# MIPI_CSI.net
KiCad netlist of a schematic drawn in Altium Designer
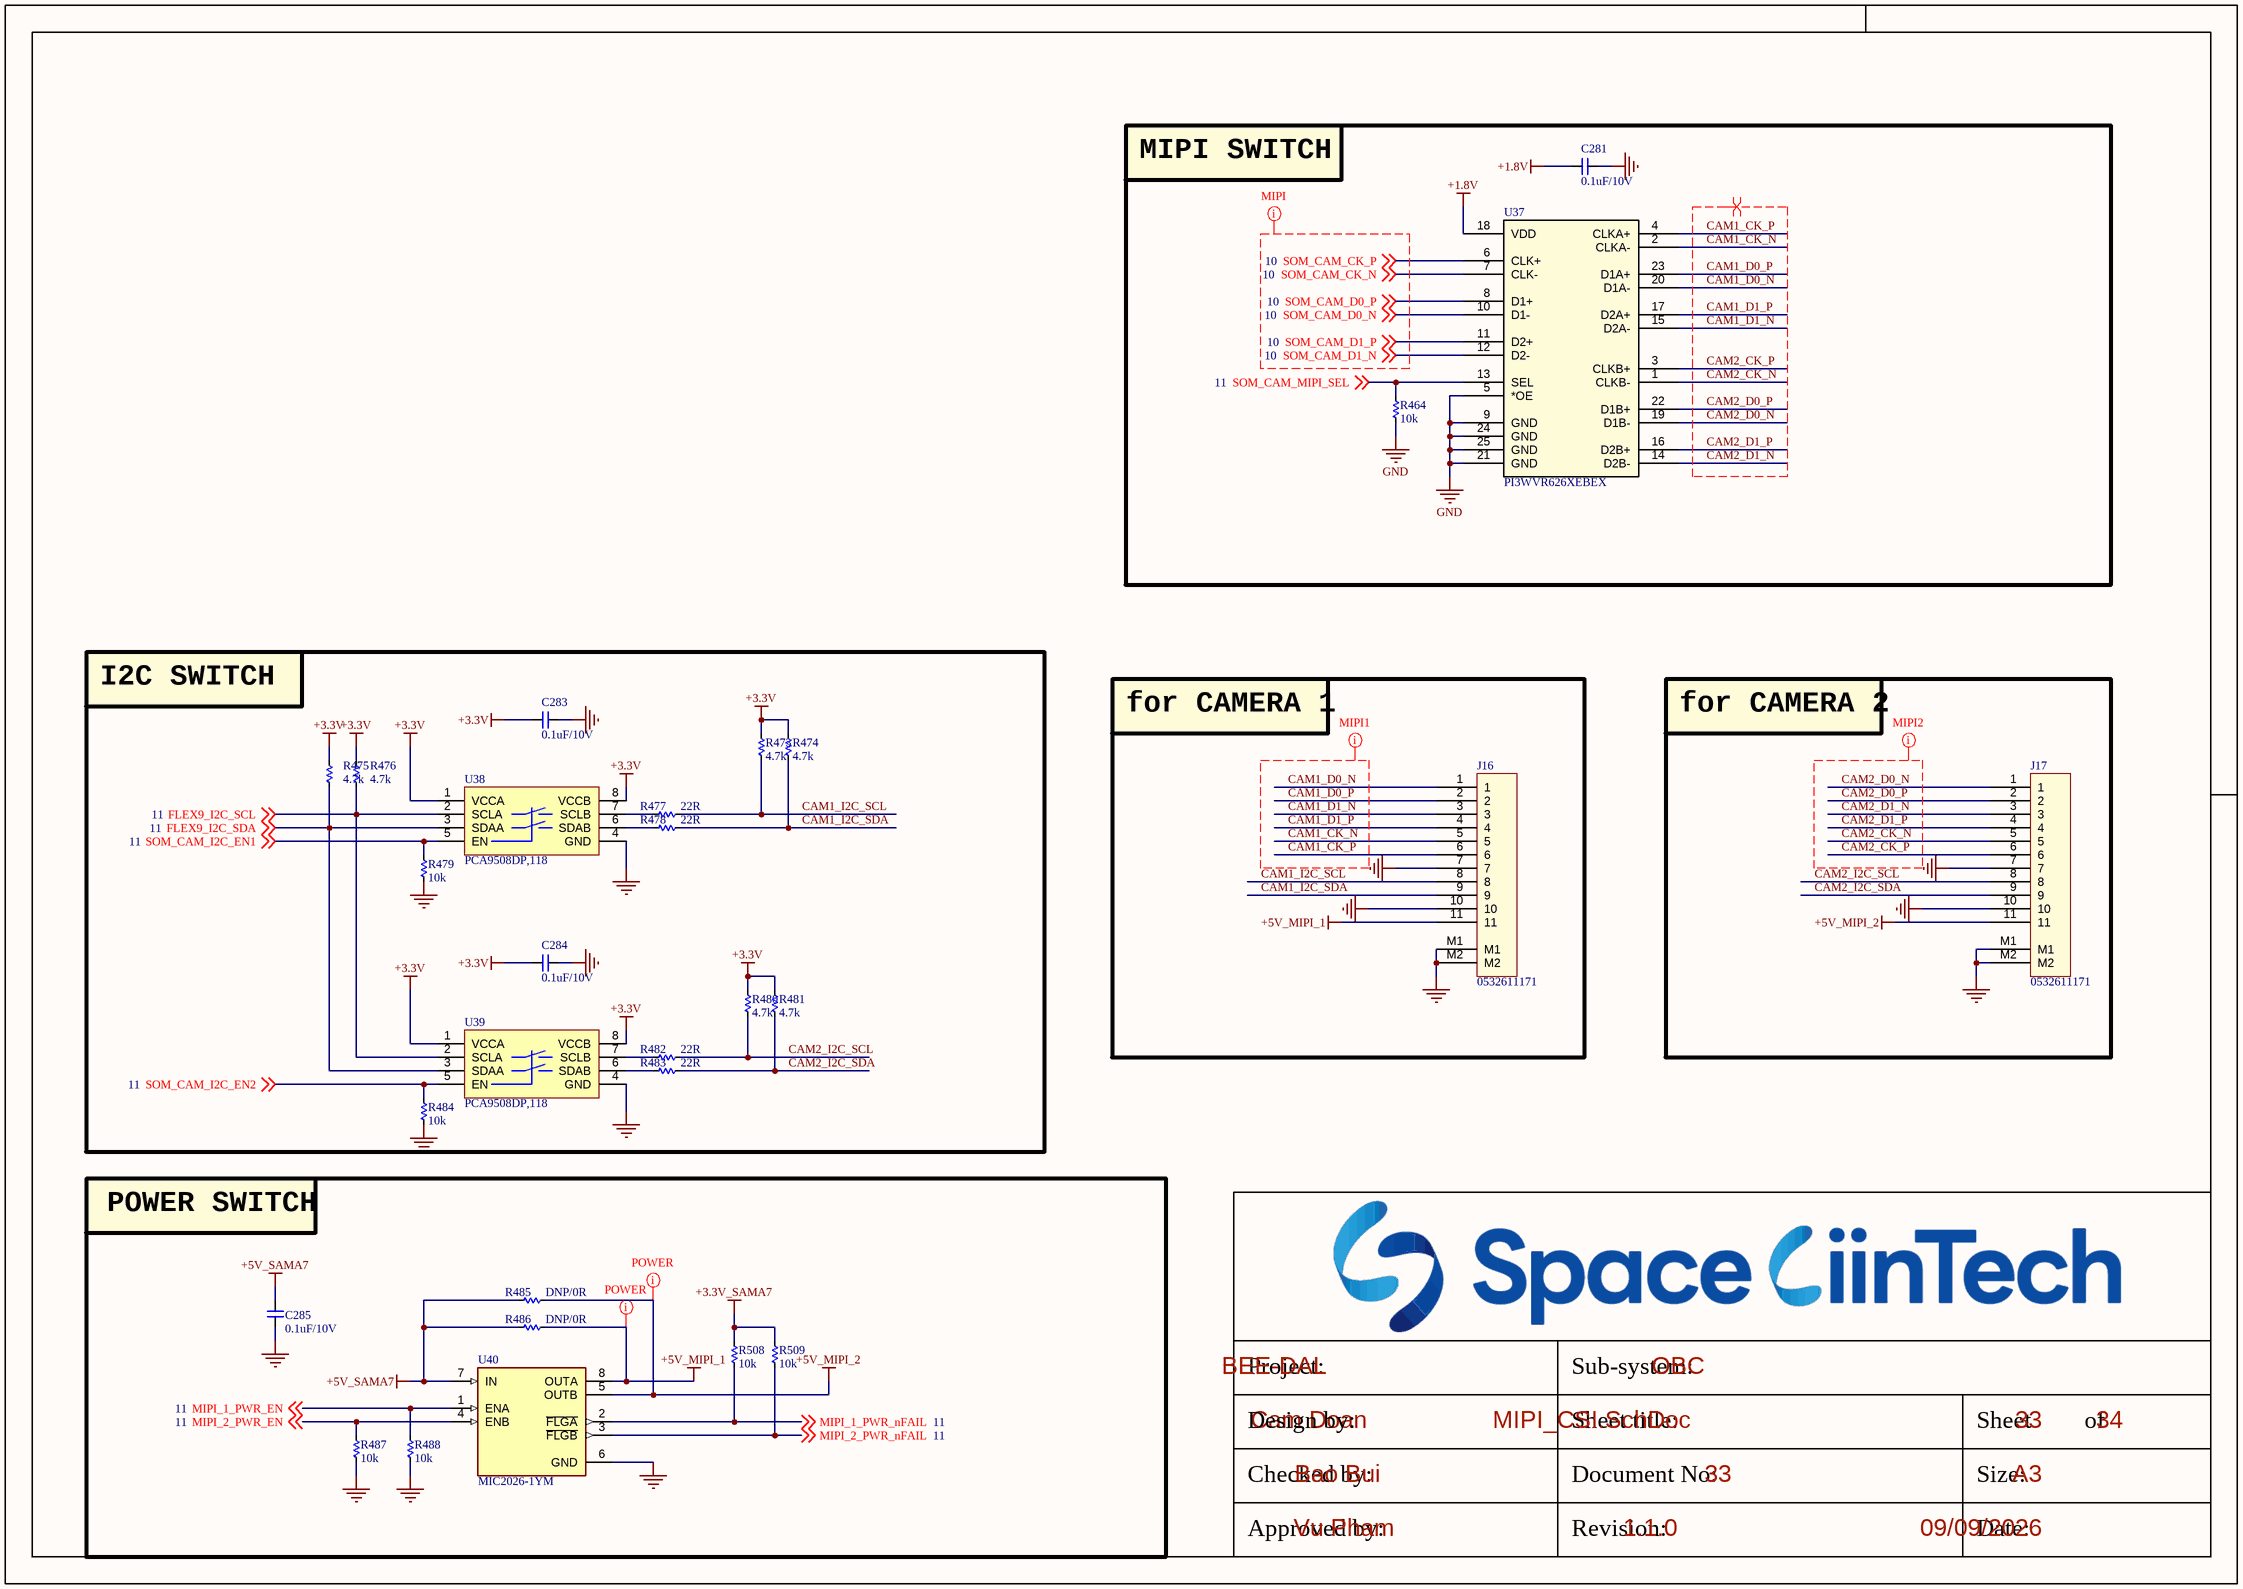
[diagram p0: MIPI_CSI.SchDoc]

(export (version "E")
  (design (tool "Eeschema 10.0.6"))
  (components
    (comp (ref "C281")
      (value "0.1uF/10V")
      (footprint "CAP_C_1005X50_L")
      (description "CAP CHIP")
      (libsource (lib "LABLIB") (part "_CAP_C_2"))
    )
    (comp (ref "C283")
      (value "0.1uF/10V")
      (footprint "CAP_C_1005X50_L")
      (description "CAP CHIP")
      (libsource (lib "LABLIB") (part "_CAP_C_2"))
    )
    (comp (ref "C284")
      (value "0.1uF/10V")
      (footprint "CAP_C_1005X50_L")
      (description "CAP CHIP")
      (libsource (lib "LABLIB") (part "_CAP_C_2"))
    )
    (comp (ref "C285")
      (value "0.1uF/10V")
      (footprint "CAP_C_1005X50_L")
      (description "CAP")
      (libsource (lib "LABLIB") (part "_CAP_C_2"))
    )
    (comp (ref "J16")
      (value "0532611171")
      (footprint "MOLEX_0532611171")
      (libsource (lib "LABLIB") (part "Header 11x1_2M"))
    )
    (comp (ref "J17")
      (value "0532611171")
      (footprint "MOLEX_0532611171")
      (libsource (lib "LABLIB") (part "Header 11x1_2M"))
    )
    (comp (ref "R464")
      (value "10k")
      (footprint "RES_C_1005X40")
      (description "RES")
      (libsource (lib "LABLIB") (part "_RES_B_2"))
    )
    (comp (ref "R473")
      (value "4.7k")
      (footprint "RES_C_1005X40")
      (description "RES")
      (libsource (lib "LABLIB") (part "_RES_B_2"))
    )
    (comp (ref "R474")
      (value "4.7k")
      (footprint "RES_C_1005X40")
      (description "RES")
      (libsource (lib "LABLIB") (part "_RES_B_2"))
    )
    (comp (ref "R475")
      (value "4.7k")
      (footprint "RES_C_1005X40")
      (description "RES")
      (libsource (lib "LABLIB") (part "_RES_B_2"))
    )
    (comp (ref "R476")
      (value "4.7k")
      (footprint "RES_C_1005X40")
      (description "RES")
      (libsource (lib "LABLIB") (part "_RES_B_2"))
    )
    (comp (ref "R477")
      (value "22R")
      (footprint "RES_C_1005X40")
      (description "RES")
      (libsource (lib "LABLIB") (part "_RES_B_2"))
    )
    (comp (ref "R478")
      (value "22R")
      (footprint "RES_C_1005X40")
      (description "RES")
      (libsource (lib "LABLIB") (part "_RES_B_2"))
    )
    (comp (ref "R479")
      (value "10k")
      (footprint "RES_C_1005X40")
      (description "RES")
      (libsource (lib "LABLIB") (part "_RES_B_2"))
    )
    (comp (ref "R480")
      (value "4.7k")
      (footprint "RES_C_1005X40")
      (description "RES")
      (libsource (lib "LABLIB") (part "_RES_B_2"))
    )
    (comp (ref "R481")
      (value "4.7k")
      (footprint "RES_C_1005X40")
      (description "RES")
      (libsource (lib "LABLIB") (part "_RES_B_2"))
    )
    (comp (ref "R482")
      (value "22R")
      (footprint "RES_C_1005X40")
      (description "RES")
      (libsource (lib "LABLIB") (part "_RES_B_2"))
    )
    (comp (ref "R483")
      (value "22R")
      (footprint "RES_C_1005X40")
      (description "RES")
      (libsource (lib "LABLIB") (part "_RES_B_2"))
    )
    (comp (ref "R484")
      (value "10k")
      (footprint "RES_C_1005X40")
      (description "RES")
      (libsource (lib "LABLIB") (part "_RES_B_2"))
    )
    (comp (ref "R485")
      (value "DNP/0R")
      (footprint "RES_C_1005X40")
      (description "RES")
      (libsource (lib "LABLIB") (part "_RES_B_2"))
    )
    (comp (ref "R486")
      (value "DNP/0R")
      (footprint "RES_C_1005X40")
      (description "RES")
      (libsource (lib "LABLIB") (part "_RES_B_2"))
    )
    (comp (ref "R487")
      (value "10k")
      (footprint "RES_C_1005X40")
      (description "RES")
      (libsource (lib "LABLIB") (part "_RES_B_2"))
    )
    (comp (ref "R488")
      (value "10k")
      (footprint "RES_C_1005X40")
      (description "RES")
      (libsource (lib "LABLIB") (part "_RES_B_2"))
    )
    (comp (ref "R508")
      (value "10k")
      (footprint "RES_C_1005X40")
      (description "RES")
      (libsource (lib "LABLIB") (part "_RES_B_2"))
    )
    (comp (ref "R509")
      (value "10k")
      (footprint "RES_C_1005X40")
      (description "RES")
      (libsource (lib "LABLIB") (part "_RES_B_2"))
    )
    (comp (ref "U37")
      (value "PI3WVR626XEBEX")
      (footprint "PI3WVR626XEBEX_DIO")
      (libsource (lib "CAMERA_SchLib") (part "PI3WVR626XEBEX"))
    )
    (comp (ref "U38")
      (value "PCA9508DP,118")
      (footprint "TSOP8")
      (libsource (lib "EXP_HW_V3") (part "PCA9508DP,118"))
    )
    (comp (ref "U39")
      (value "PCA9508DP,118")
      (footprint "TSOP8")
      (libsource (lib "EXP_HW_V3") (part "PCA9508DP,118"))
    )
    (comp (ref "U40")
      (value "MIC2026-1YM")
      (footprint "SOIC127P602X173-8N")
      (description "Power Switch/Driver 1:2 N-Channel 1.25A 8-SOIC")
      (fields (field (name "MF") "Microchip"))
      (libsource (lib "LABLIB") (part "IC_PWRSW_MIC2026-1YM"))
    )
  )
  (nets
    (net (code "1") (name "+1.8V") (class "Default")
      (node (ref "C281") (pin "2") (pinfunction "2_2") (pintype "passive"))
      (node (ref "U37") (pin "18") (pinfunction "VDD_18") (pintype "passive"))
    )
    (net (code "2") (name "+3.3V") (class "Default")
      (node (ref "C283") (pin "2") (pinfunction "2_2") (pintype "passive"))
      (node (ref "C284") (pin "2") (pinfunction "2_2") (pintype "passive"))
      (node (ref "R473") (pin "1") (pinfunction "1_1") (pintype "passive"))
      (node (ref "R474") (pin "1") (pinfunction "1_1") (pintype "passive"))
      (node (ref "R475") (pin "1") (pinfunction "1_1") (pintype "passive"))
      (node (ref "R476") (pin "1") (pinfunction "1_1") (pintype "passive"))
      (node (ref "R480") (pin "1") (pinfunction "1_1") (pintype "passive"))
      (node (ref "R481") (pin "1") (pinfunction "1_1") (pintype "passive"))
      (node (ref "U38") (pin "1") (pinfunction "VCCA_1") (pintype "passive"))
      (node (ref "U38") (pin "8") (pinfunction "VCCB_8") (pintype "passive"))
      (node (ref "U39") (pin "1") (pinfunction "VCCA_1") (pintype "passive"))
      (node (ref "U39") (pin "8") (pinfunction "VCCB_8") (pintype "passive"))
    )
    (net (code "3") (name "+3.3V_SAMA7") (class "Default")
      (node (ref "R508") (pin "1") (pinfunction "1_1") (pintype "passive"))
      (node (ref "R509") (pin "1") (pinfunction "1_1") (pintype "passive"))
    )
    (net (code "4") (name "+5V_MIPI_1") (class "Default")
      (node (ref "J16") (pin "11") (pinfunction "11_11") (pintype "passive"))
      (node (ref "R486") (pin "1") (pinfunction "1_1") (pintype "passive"))
      (node (ref "U40") (pin "8") (pinfunction "OUTA_8") (pintype "passive"))
    )
    (net (code "5") (name "+5V_MIPI_2") (class "Default")
      (node (ref "J17") (pin "11") (pinfunction "11_11") (pintype "passive"))
      (node (ref "R485") (pin "1") (pinfunction "1_1") (pintype "passive"))
      (node (ref "U40") (pin "5") (pinfunction "OUTB_5") (pintype "passive"))
    )
    (net (code "6") (name "+5V_SAMA7") (class "Default")
      (node (ref "C285") (pin "2") (pinfunction "2_2") (pintype "passive"))
      (node (ref "R485") (pin "2") (pinfunction "2_2") (pintype "passive"))
      (node (ref "R486") (pin "2") (pinfunction "2_2") (pintype "passive"))
      (node (ref "U40") (pin "7") (pinfunction "IN_7") (pintype "input"))
    )
    (net (code "7") (name "/CAM1_CK_N") (class "Default")
      (node (ref "J16") (pin "5") (pinfunction "5_5") (pintype "passive"))
      (node (ref "U37") (pin "2") (pinfunction "CLKA-_2") (pintype "passive"))
    )
    (net (code "8") (name "/CAM1_CK_P") (class "Default")
      (node (ref "J16") (pin "6") (pinfunction "6_6") (pintype "passive"))
      (node (ref "U37") (pin "4") (pinfunction "CLKA+_4") (pintype "passive"))
    )
    (net (code "9") (name "/CAM1_D0_N") (class "Default")
      (node (ref "J16") (pin "1") (pinfunction "1_1") (pintype "passive"))
      (node (ref "U37") (pin "20") (pinfunction "D1A-_20") (pintype "passive"))
    )
    (net (code "10") (name "/CAM1_D0_P") (class "Default")
      (node (ref "J16") (pin "2") (pinfunction "2_2") (pintype "passive"))
      (node (ref "U37") (pin "23") (pinfunction "D1A+_23") (pintype "passive"))
    )
    (net (code "11") (name "/CAM1_D1_N") (class "Default")
      (node (ref "J16") (pin "3") (pinfunction "3_3") (pintype "passive"))
      (node (ref "U37") (pin "15") (pinfunction "D2A-_15") (pintype "passive"))
    )
    (net (code "12") (name "/CAM1_D1_P") (class "Default")
      (node (ref "J16") (pin "4") (pinfunction "4_4") (pintype "passive"))
      (node (ref "U37") (pin "17") (pinfunction "D2A+_17") (pintype "passive"))
    )
    (net (code "13") (name "/CAM1_I2C_SCL") (class "Default")
      (node (ref "J16") (pin "8") (pinfunction "8_8") (pintype "passive"))
      (node (ref "R473") (pin "2") (pinfunction "2_2") (pintype "passive"))
      (node (ref "R477") (pin "2") (pinfunction "2_2") (pintype "passive"))
    )
    (net (code "14") (name "/CAM1_I2C_SDA") (class "Default")
      (node (ref "J16") (pin "9") (pinfunction "9_9") (pintype "passive"))
      (node (ref "R474") (pin "2") (pinfunction "2_2") (pintype "passive"))
      (node (ref "R478") (pin "2") (pinfunction "2_2") (pintype "passive"))
    )
    (net (code "15") (name "/CAM2_CK_N") (class "Default")
      (node (ref "J17") (pin "5") (pinfunction "5_5") (pintype "passive"))
      (node (ref "U37") (pin "1") (pinfunction "CLKB-_1") (pintype "passive"))
    )
    (net (code "16") (name "/CAM2_CK_P") (class "Default")
      (node (ref "J17") (pin "6") (pinfunction "6_6") (pintype "passive"))
      (node (ref "U37") (pin "3") (pinfunction "CLKB+_3") (pintype "passive"))
    )
    (net (code "17") (name "/CAM2_D0_N") (class "Default")
      (node (ref "J17") (pin "1") (pinfunction "1_1") (pintype "passive"))
      (node (ref "U37") (pin "19") (pinfunction "D1B-_19") (pintype "passive"))
    )
    (net (code "18") (name "/CAM2_D0_P") (class "Default")
      (node (ref "J17") (pin "2") (pinfunction "2_2") (pintype "passive"))
      (node (ref "U37") (pin "22") (pinfunction "D1B+_22") (pintype "passive"))
    )
    (net (code "19") (name "/CAM2_D1_N") (class "Default")
      (node (ref "J17") (pin "3") (pinfunction "3_3") (pintype "passive"))
      (node (ref "U37") (pin "14") (pinfunction "D2B-_14") (pintype "passive"))
    )
    (net (code "20") (name "/CAM2_D1_P") (class "Default")
      (node (ref "J17") (pin "4") (pinfunction "4_4") (pintype "passive"))
      (node (ref "U37") (pin "16") (pinfunction "D2B+_16") (pintype "passive"))
    )
    (net (code "21") (name "/CAM2_I2C_SCL") (class "Default")
      (node (ref "J17") (pin "8") (pinfunction "8_8") (pintype "passive"))
      (node (ref "R480") (pin "2") (pinfunction "2_2") (pintype "passive"))
      (node (ref "R482") (pin "2") (pinfunction "2_2") (pintype "passive"))
    )
    (net (code "22") (name "/CAM2_I2C_SDA") (class "Default")
      (node (ref "J17") (pin "9") (pinfunction "9_9") (pintype "passive"))
      (node (ref "R481") (pin "2") (pinfunction "2_2") (pintype "passive"))
      (node (ref "R483") (pin "2") (pinfunction "2_2") (pintype "passive"))
    )
    (net (code "23") (name "FLEX9_I2C_SCL") (class "Default")
      (node (ref "R476") (pin "2") (pinfunction "2_2") (pintype "passive"))
      (node (ref "U38") (pin "2") (pinfunction "SCLA_2") (pintype "passive"))
      (node (ref "U39") (pin "2") (pinfunction "SCLA_2") (pintype "passive"))
    )
    (net (code "24") (name "FLEX9_I2C_SDA") (class "Default")
      (node (ref "R475") (pin "2") (pinfunction "2_2") (pintype "passive"))
      (node (ref "U38") (pin "3") (pinfunction "SDAA_3") (pintype "passive"))
      (node (ref "U39") (pin "3") (pinfunction "SDAA_3") (pintype "passive"))
    )
    (net (code "25") (name "GND") (class "Default")
      (node (ref "C281") (pin "1") (pinfunction "1_1") (pintype "passive"))
      (node (ref "C283") (pin "1") (pinfunction "1_1") (pintype "passive"))
      (node (ref "C284") (pin "1") (pinfunction "1_1") (pintype "passive"))
      (node (ref "C285") (pin "1") (pinfunction "1_1") (pintype "passive"))
      (node (ref "J16") (pin "10") (pinfunction "10_10") (pintype "passive"))
      (node (ref "J16") (pin "7") (pinfunction "7_7") (pintype "passive"))
      (node (ref "J16") (pin "M1") (pinfunction "M1_M1") (pintype "passive"))
      (node (ref "J16") (pin "M2") (pinfunction "M2_M2") (pintype "passive"))
      (node (ref "J17") (pin "10") (pinfunction "10_10") (pintype "passive"))
      (node (ref "J17") (pin "7") (pinfunction "7_7") (pintype "passive"))
      (node (ref "J17") (pin "M1") (pinfunction "M1_M1") (pintype "passive"))
      (node (ref "J17") (pin "M2") (pinfunction "M2_M2") (pintype "passive"))
      (node (ref "R464") (pin "1") (pinfunction "1_1") (pintype "passive"))
      (node (ref "R479") (pin "2") (pinfunction "2_2") (pintype "passive"))
      (node (ref "R484") (pin "2") (pinfunction "2_2") (pintype "passive"))
      (node (ref "R487") (pin "2") (pinfunction "2_2") (pintype "passive"))
      (node (ref "R488") (pin "2") (pinfunction "2_2") (pintype "passive"))
      (node (ref "U37") (pin "21") (pinfunction "GND_21") (pintype "passive"))
      (node (ref "U37") (pin "24") (pinfunction "GND_24") (pintype "passive"))
      (node (ref "U37") (pin "25") (pinfunction "GND_25") (pintype "passive"))
      (node (ref "U37") (pin "5") (pinfunction "*OE_5") (pintype "passive"))
      (node (ref "U37") (pin "9") (pinfunction "GND_9") (pintype "passive"))
      (node (ref "U38") (pin "4") (pinfunction "GND_4") (pintype "passive"))
      (node (ref "U39") (pin "4") (pinfunction "GND_4") (pintype "passive"))
      (node (ref "U40") (pin "6") (pinfunction "GND_6") (pintype "power_in"))
    )
    (net (code "26") (name "MIPI_1_PWR_EN") (class "Default")
      (node (ref "R488") (pin "1") (pinfunction "1_1") (pintype "passive"))
      (node (ref "U40") (pin "1") (pinfunction "ENA_1") (pintype "input"))
    )
    (net (code "27") (name "MIPI_1_PWR_nFAIL") (class "Default")
      (node (ref "R508") (pin "2") (pinfunction "2_2") (pintype "passive"))
      (node (ref "U40") (pin "2") (pinfunction "~{FLGA}_2") (pintype "output"))
    )
    (net (code "28") (name "MIPI_2_PWR_EN") (class "Default")
      (node (ref "R487") (pin "1") (pinfunction "1_1") (pintype "passive"))
      (node (ref "U40") (pin "4") (pinfunction "ENB_4") (pintype "input"))
    )
    (net (code "29") (name "MIPI_2_PWR_nFAIL") (class "Default")
      (node (ref "R509") (pin "2") (pinfunction "2_2") (pintype "passive"))
      (node (ref "U40") (pin "3") (pinfunction "~{FLGB}_3") (pintype "output"))
    )
    (net (code "30") (name "Net-(U38-SCLB)") (class "Default")
      (node (ref "R477") (pin "1") (pinfunction "1_1") (pintype "passive"))
      (node (ref "U38") (pin "7") (pinfunction "SCLB_7") (pintype "passive"))
    )
    (net (code "31") (name "Net-(U38-SDAB)") (class "Default")
      (node (ref "R478") (pin "1") (pinfunction "1_1") (pintype "passive"))
      (node (ref "U38") (pin "6") (pinfunction "SDAB_6") (pintype "passive"))
    )
    (net (code "32") (name "Net-(U39-SCLB)") (class "Default")
      (node (ref "R482") (pin "1") (pinfunction "1_1") (pintype "passive"))
      (node (ref "U39") (pin "7") (pinfunction "SCLB_7") (pintype "passive"))
    )
    (net (code "33") (name "Net-(U39-SDAB)") (class "Default")
      (node (ref "R483") (pin "1") (pinfunction "1_1") (pintype "passive"))
      (node (ref "U39") (pin "6") (pinfunction "SDAB_6") (pintype "passive"))
    )
    (net (code "34") (name "SOM_CAM_CK_N") (class "Default")
      (node (ref "U37") (pin "7") (pinfunction "CLK-_7") (pintype "passive"))
    )
    (net (code "35") (name "SOM_CAM_CK_P") (class "Default")
      (node (ref "U37") (pin "6") (pinfunction "CLK+_6") (pintype "passive"))
    )
    (net (code "36") (name "SOM_CAM_D0_N") (class "Default")
      (node (ref "U37") (pin "10") (pinfunction "D1-_10") (pintype "passive"))
    )
    (net (code "37") (name "SOM_CAM_D0_P") (class "Default")
      (node (ref "U37") (pin "8") (pinfunction "D1+_8") (pintype "passive"))
    )
    (net (code "38") (name "SOM_CAM_D1_N") (class "Default")
      (node (ref "U37") (pin "12") (pinfunction "D2-_12") (pintype "passive"))
    )
    (net (code "39") (name "SOM_CAM_D1_P") (class "Default")
      (node (ref "U37") (pin "11") (pinfunction "D2+_11") (pintype "passive"))
    )
    (net (code "40") (name "SOM_CAM_I2C_EN1") (class "Default")
      (node (ref "R479") (pin "1") (pinfunction "1_1") (pintype "passive"))
      (node (ref "U38") (pin "5") (pinfunction "EN_5") (pintype "passive"))
    )
    (net (code "41") (name "SOM_CAM_I2C_EN2") (class "Default")
      (node (ref "R484") (pin "1") (pinfunction "1_1") (pintype "passive"))
      (node (ref "U39") (pin "5") (pinfunction "EN_5") (pintype "passive"))
    )
    (net (code "42") (name "SOM_CAM_MIPI_SEL") (class "Default")
      (node (ref "R464") (pin "2") (pinfunction "2_2") (pintype "passive"))
      (node (ref "U37") (pin "13") (pinfunction "SEL_13") (pintype "passive"))
    )
  )
)
